# Power.net
KiCad netlist of a schematic drawn in Altium Designer
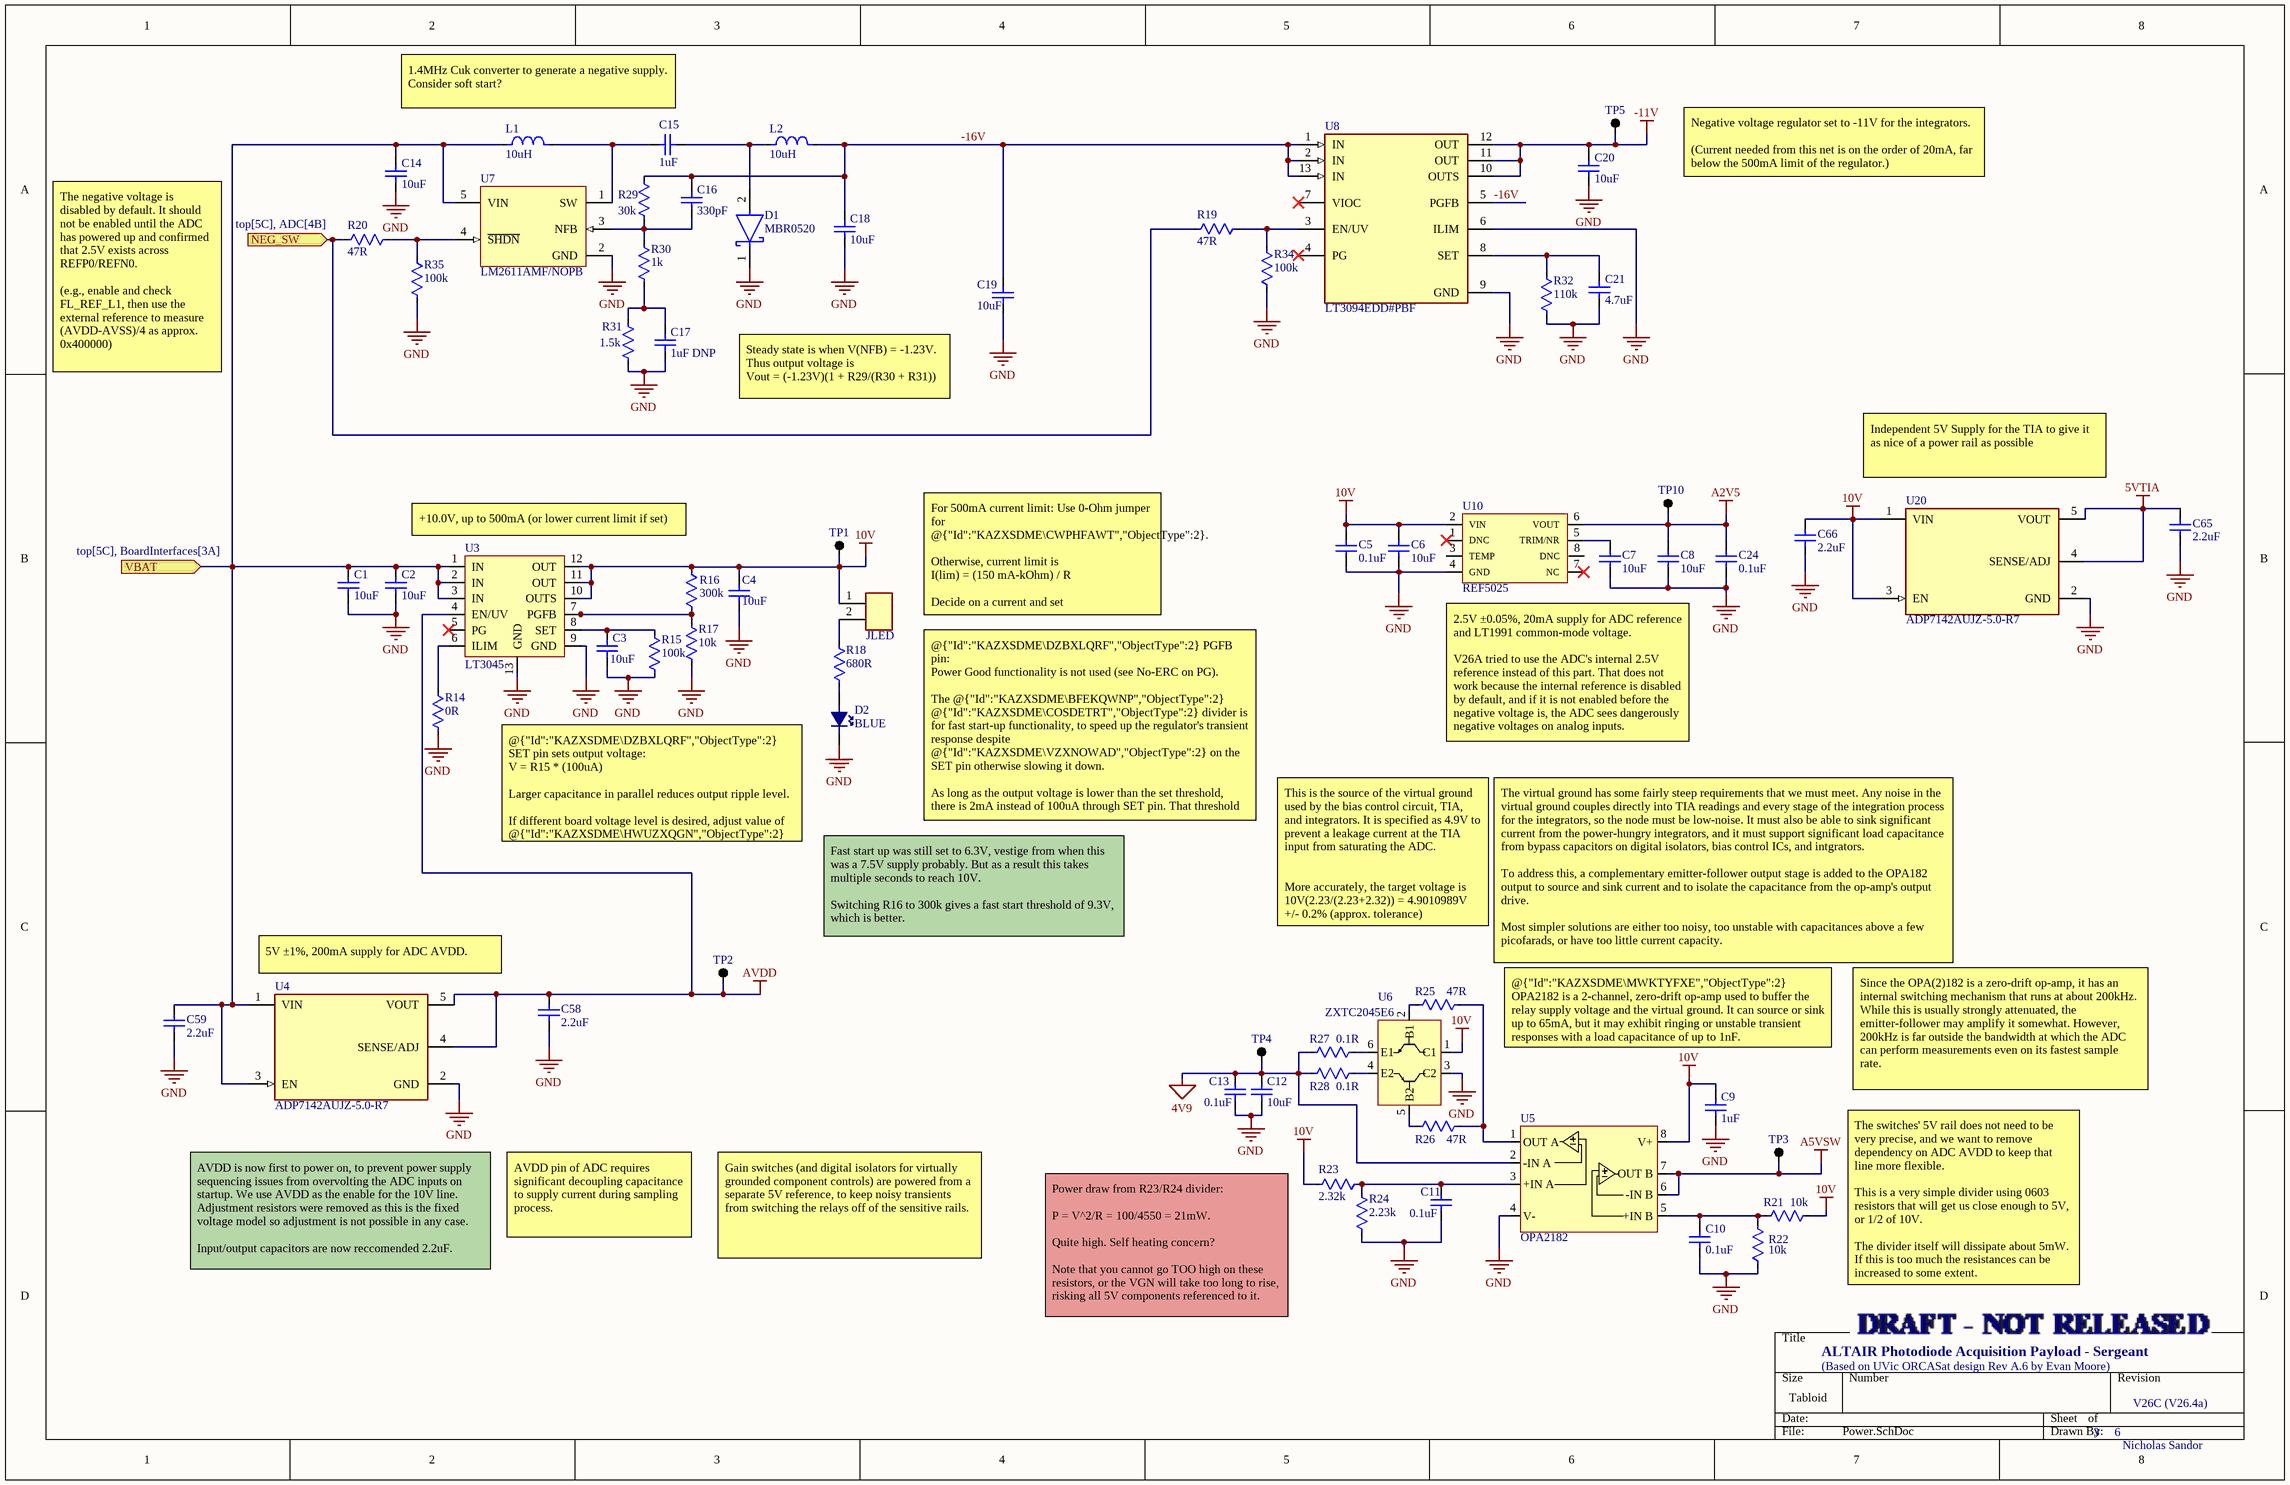
[diagram p0: Power.SchDoc]

(export (version "E")
  (design (tool "Eeschema 10.0.6"))
  (components
    (comp (ref "C1")
      (value "10uF")
      (footprint "CAP 1206 IPC LOW DENSITY")
      (description "Murata GRT319R6YA106KE01D - Cap Ceramic 10uF 35V X5R 10% Pad SMD 1206 85C Automotive T/R")
      (fields (field (name "MF") "Murata") (field (name "MP") "GRT319R6YA106KE01D"))
      (libsource (lib "ALTAIR_PD_Capacitors") (part "CAP"))
    )
    (comp (ref "C2")
      (value "10uF")
      (footprint "CAP 1206 IPC LOW DENSITY")
      (description "Murata GRT319R6YA106KE01D - Cap Ceramic 10uF 35V X5R 10% Pad SMD 1206 85C Automotive T/R")
      (fields (field (name "MF") "Murata") (field (name "MP") "GRT319R6YA106KE01D"))
      (libsource (lib "ALTAIR_PD_Capacitors") (part "CAP"))
    )
    (comp (ref "C3")
      (value "10uF")
      (footprint "CAP 1206 IPC LOW DENSITY")
      (description "Murata GRT319R6YA106KE01D - Cap Ceramic 10uF 35V X5R 10% Pad SMD 1206 85C Automotive T/R")
      (fields (field (name "MF") "Murata") (field (name "MP") "GRT319R6YA106KE01D"))
      (libsource (lib "ALTAIR_PD_Capacitors") (part "CAP"))
    )
    (comp (ref "C4")
      (value "10uF")
      (footprint "CAP 1206 IPC LOW DENSITY")
      (description "Murata GRT319R6YA106KE01D - Cap Ceramic 10uF 35V X5R 10% Pad SMD 1206 85C Automotive T/R")
      (fields (field (name "MF") "Murata") (field (name "MP") "GRT319R6YA106KE01D"))
      (libsource (lib "ALTAIR_PD_Capacitors") (part "CAP"))
    )
    (comp (ref "C5")
      (value "0.1uF")
      (footprint "CAP 0603 IPC MID DENSITY")
      (description "Kemet C0603C104K5RACAUTO - Cap Ceramic 0.1uF 50V X7R 10% 0603 125C Paper T/R")
      (fields (field (name "MF") "Kemet") (field (name "MP") "C0603C104K5RACAUTO"))
      (libsource (lib "ALTAIR_PD_Capacitors") (part "CAP"))
    )
    (comp (ref "C6")
      (value "10uF")
      (footprint "CAP 0805 IPC MID DENSITY")
      (description "Murata GRM21BR61E106KA73L - Cap Ceramic 10uF 10% 25V X5R 0805")
      (fields (field (name "MF") "Murata") (field (name "MP") "GRM21BR61E106KA73L"))
      (libsource (lib "ALTAIR_PD_Capacitors") (part "CAP"))
    )
    (comp (ref "C7")
      (value "10uF")
      (footprint "CAP 0805 IPC MID DENSITY")
      (description "Murata GRM21BR61E106KA73L - Cap Ceramic 10uF 10% 25V X5R 0805")
      (fields (field (name "MF") "Murata") (field (name "MP") "GRM21BR61E106KA73L"))
      (libsource (lib "ALTAIR_PD_Capacitors") (part "CAP"))
    )
    (comp (ref "C8")
      (value "10uF")
      (footprint "CAP 0805 IPC MID DENSITY")
      (description "Murata GRM21BR61E106KA73L - Cap Ceramic 10uF 10% 25V X5R 0805")
      (fields (field (name "MF") "Murata") (field (name "MP") "GRM21BR61E106KA73L"))
      (libsource (lib "ALTAIR_PD_Capacitors") (part "CAP"))
    )
    (comp (ref "C9")
      (value "1uF")
      (footprint "CAP 0603 IPC MID DENSITY")
      (description "Murata GRT188R61H105KE13D - Cap MLCC AEC-Q200 X5R 1uF 50V 0603")
      (fields (field (name "MF") "Murata") (field (name "MP") "GRT188R61H105KE13D"))
      (libsource (lib "ALTAIR_PD_Capacitors") (part "CAP"))
    )
    (comp (ref "C10")
      (value "0.1uF")
      (footprint "CAP 0603 IPC MID DENSITY")
      (description "Kemet C0603C104K5RACAUTO - Cap Ceramic 0.1uF 50V X7R 10% 0603 125C Paper T/R")
      (fields (field (name "MF") "Kemet") (field (name "MP") "C0603C104K5RACAUTO"))
      (libsource (lib "ALTAIR_PD_Capacitors") (part "CAP"))
    )
    (comp (ref "C11")
      (value "0.1uF")
      (footprint "CAP 0603 IPC MID DENSITY")
      (description "Kemet C0603C104K5RACAUTO - Cap Ceramic 0.1uF 50V X7R 10% 0603 125C Paper T/R")
      (fields (field (name "MF") "Kemet") (field (name "MP") "C0603C104K5RACAUTO"))
      (libsource (lib "ALTAIR_PD_Capacitors") (part "CAP"))
    )
    (comp (ref "C12")
      (value "10uF")
      (footprint "CAP 1206 IPC LOW DENSITY")
      (description "Murata GRT319R6YA106KE01D - Cap Ceramic 10uF 35V X5R 10% Pad SMD 1206 85C Automotive T/R")
      (fields (field (name "MF") "Murata") (field (name "MP") "GRT319R6YA106KE01D"))
      (libsource (lib "ALTAIR_PD_Capacitors") (part "CAP"))
    )
    (comp (ref "C13")
      (value "0.1uF")
      (footprint "CAP 0603 IPC MID DENSITY")
      (description "Kemet C0603C104K5RACAUTO - Cap Ceramic 0.1uF 50V X7R 10% 0603 125C Paper T/R")
      (fields (field (name "MF") "Kemet") (field (name "MP") "C0603C104K5RACAUTO"))
      (libsource (lib "ALTAIR_PD_Capacitors") (part "CAP"))
    )
    (comp (ref "C14")
      (value "10uF")
      (footprint "CAP 0805 IPC MID DENSITY")
      (description "Murata GRM21BR61E106KA73L - Cap Ceramic 10uF 10% 25V X5R 0805")
      (fields (field (name "MF") "Murata") (field (name "MP") "GRM21BR61E106KA73L"))
      (libsource (lib "ALTAIR_PD_Capacitors") (part "CAP"))
    )
    (comp (ref "C15")
      (value "1uF")
      (footprint "CAP 0603 IPC MID DENSITY")
      (description "Murata GRT188R61H105KE13D - Cap MLCC AEC-Q200 X5R 1uF 50V 0603")
      (fields (field (name "MF") "Murata") (field (name "MP") "GRT188R61H105KE13D"))
      (libsource (lib "ALTAIR_PD_Capacitors") (part "CAP"))
    )
    (comp (ref "C16")
      (value "330pF")
      (footprint "CAP 1206 NON-IPC KEMET NP0")
      (description "Kemet C1206C331J5GACTU - Cap Ceramic 330pF 50V 5% NP0 1206")
      (fields (field (name "MF") "Kemet") (field (name "MP") "C1206C331J5GACTU"))
      (libsource (lib "ALTAIR_PD_Capacitors") (part "CAP"))
    )
    (comp (ref "C17")
      (value "1uF DNP")
      (footprint "CAP 0603 IPC MID DENSITY")
      (description "Murata GRT188R61H105KE13D - Cap MLCC AEC-Q200 X5R 1uF 50V 0603")
      (fields (field (name "MF") "Murata") (field (name "MP") "GRT188R61H105KE13D"))
      (libsource (lib "ALTAIR_PD_Capacitors") (part "CAP"))
    )
    (comp (ref "C18")
      (value "10uF")
      (footprint "CAP 0805 IPC MID DENSITY")
      (description "Murata GRM21BR61E106KA73L - Cap Ceramic 10uF 10% 25V X5R 0805")
      (fields (field (name "MF") "Murata") (field (name "MP") "GRM21BR61E106KA73L"))
      (libsource (lib "ALTAIR_PD_Capacitors") (part "CAP"))
    )
    (comp (ref "C19")
      (value "10uF")
      (footprint "CAP 0805 IPC MID DENSITY")
      (description "Murata GRM21BR61E106KA73L - Cap Ceramic 10uF 10% 25V X5R 0805")
      (fields (field (name "MF") "Murata") (field (name "MP") "GRM21BR61E106KA73L"))
      (libsource (lib "ALTAIR_PD_Capacitors") (part "CAP"))
    )
    (comp (ref "C20")
      (value "10uF")
      (footprint "CAP 0805 IPC MID DENSITY")
      (description "Murata GRM21BR61E106KA73L - Cap Ceramic 10uF 10% 25V X5R 0805")
      (fields (field (name "MF") "Murata") (field (name "MP") "GRM21BR61E106KA73L"))
      (libsource (lib "ALTAIR_PD_Capacitors") (part "CAP"))
    )
    (comp (ref "C21")
      (value "4.7uF")
      (footprint "CAP 0805 NON-IPC KEMET X5R")
      (description "Kemet C0805C475K8PACTU - Cap Ceramic 4.7uF 10V X5R 0805")
      (fields (field (name "MF") "Kemet") (field (name "MP") "C0805C475K8PACTU"))
      (libsource (lib "ALTAIR_PD_Capacitors") (part "CAP"))
    )
    (comp (ref "C24")
      (value "0.1uF")
      (footprint "CAP 0603 IPC MID DENSITY")
      (description "Kemet C0603C104K5RACAUTO - Cap Ceramic 0.1uF 50V X7R 10% 0603 125C Paper T/R")
      (fields (field (name "MF") "Kemet") (field (name "MP") "C0603C104K5RACAUTO"))
      (libsource (lib "ALTAIR_PD_Capacitors") (part "CAP"))
    )
    (comp (ref "C58")
      (value "2.2uF")
      (footprint "CAP 1206 UNKNOWN")
      (description "Cap, Nonpolar, Any, Must choose footprint manually")
      (libsource (lib "ALTAIR_PD_Capacitors") (part "CAP"))
    )
    (comp (ref "C59")
      (value "2.2uF")
      (footprint "CAP 1206 UNKNOWN")
      (description "Cap, Nonpolar, Any, Must choose footprint manually")
      (libsource (lib "ALTAIR_PD_Capacitors") (part "CAP"))
    )
    (comp (ref "C65")
      (value "2.2uF")
      (footprint "CAP 1206 UNKNOWN")
      (description "Cap, Nonpolar, Any, Must choose footprint manually")
      (libsource (lib "ALTAIR_PD_Capacitors") (part "CAP"))
    )
    (comp (ref "C66")
      (value "2.2uF")
      (footprint "CAP 1206 UNKNOWN")
      (description "Cap, Nonpolar, Any, Must choose footprint manually")
      (libsource (lib "ALTAIR_PD_Capacitors") (part "CAP"))
    )
    (comp (ref "D1")
      (value "MBR0520")
      (footprint "SOD-123 ONSEMI SMALL PADS")
      (description "DIODE SCHOTTKY 20V 500MA SOD123")
      (fields (field (name "MF") "onsemi") (field (name "MP") "MBR0520LT1G"))
      (libsource (lib "ALTAIR_PD_Diodes") (part "Schottky"))
    )
    (comp (ref "D2")
      (value "BLUE")
      (footprint "LED 0603 MID DENSITY")
      (description "LED BLUE CLEAR 0603 SMD")
      (fields (field (name "MF") "Wurth Electronics") (field (name "MP") "150060BS75000"))
      (libsource (lib "ALTAIR_PD_Diodes") (part "LED-blue"))
    )
    (comp (ref "JLED")
      (value "JLED")
      (footprint "ALTAIR_PD_Headers:JUMPER 2POS 1MM PITCH THT")
      (description "2x1 Header THT 1mm Pitch")
      (fields
        (field (name "MF") "GCT (GLOBAL CONNECTOR TECHNOLOGY)")
        (field (name "MP") "BC020-02-A-0200-0300-L-G")
      )
      (libsource (lib "ALTAIR_PD_Headers") (part "BC020-02-A-0200-0300-L-G"))
    )
    (comp (ref "L1")
      (value "10uH")
      (footprint "IND VLS3012CX-1 NONSTANDARD TDK")
      (description "TDK VLS3012CX-100M-1 - Inductor 10uH 20% 1.25A 0.324Ohm NonstandardPkg")
      (fields (field (name "TOLERANCE") "20%") (field (name "MF") "TDK Corporation"))
      (libsource (lib "ALTAIR_PD_Inductors") (part "IND"))
    )
    (comp (ref "L2")
      (value "10uH")
      (footprint "IND VLS3012CX-1 NONSTANDARD TDK")
      (description "TDK VLS3012CX-100M-1 - Inductor 10uH 20% 1.25A 0.324Ohm NonstandardPkg")
      (fields (field (name "TOLERANCE") "20%") (field (name "MF") "TDK Corporation"))
      (libsource (lib "ALTAIR_PD_Inductors") (part "IND"))
    )
    (comp (ref "R14")
      (value "0R")
      (footprint "RES 0603 IPC MID DENSITY")
      (description "Vishay CRCW06030000Z0EA - Res 0 Ohms 1/8W SMD 0603")
      (fields (field (name "MF") "Vishay Dale") (field (name "MP") "CRCW06030000Z0EA"))
      (libsource (lib "ALTAIR_PD_Resistors") (part "RES"))
    )
    (comp (ref "R15")
      (value "100k")
      (footprint "RES 0603 IPC MID DENSITY")
      (description "Panasonic ERA-3ARB104V - Res SMD 0603 0.1% 0.10W T.C. 10ppm 100K")
      (fields (field (name "MF") "Panasonic Electronic Components") (field (name "MP") "ERA-3ARB104V"))
      (libsource (lib "ALTAIR_PD_Resistors") (part "RES"))
    )
    (comp (ref "R16")
      (value "300k")
      (footprint "RES 0603 IPC MID DENSITY")
      (description "Vishay MCT06030C2003FP500 - Res SMD 200kOhm 1% 1/10W 0603")
      (fields (field (name "MF") "Vishay Dale") (field (name "MP") "MCT06030C2003FP500"))
      (libsource (lib "ALTAIR_PD_Resistors") (part "RES"))
    )
    (comp (ref "R17")
      (value "10k")
      (footprint "RES 0603 IPC MID DENSITY")
      (description "Vishay CRCW060310K0FKEA SMD 0603 10k, CRCW e3 Series, 75V, thick film, 100mW")
      (fields (field (name "MF") "Vishay Dale") (field (name "MP") "CRCW060310K0FKEA"))
      (libsource (lib "ALTAIR_PD_Resistors") (part "RES"))
    )
    (comp (ref "R18")
      (value "680R")
      (footprint "RES 0603 IPC MID DENSITY")
      (description "Panasonic ERJ-3EKF6800V - Res SMD 680 Ohm 1% 1/10W 0603")
      (fields (field (name "MF") "Panasonic Electronic Components") (field (name "MP") "ERJ-3EKF6800V"))
      (libsource (lib "ALTAIR_PD_Resistors") (part "RES"))
    )
    (comp (ref "R19")
      (value "47R")
      (footprint "RES 0603 IPC MID DENSITY")
      (description "Vishay CRCW060347R0JNEA - Res 47Ohm 5% 1/8W SMD 0603")
      (fields (field (name "MF") "Vishay Dale") (field (name "MP") "CRCW060347R0JNEA"))
      (libsource (lib "ALTAIR_PD_Resistors") (part "RES"))
    )
    (comp (ref "R20")
      (value "47R")
      (footprint "RES 0603 IPC MID DENSITY")
      (description "Vishay CRCW060347R0JNEA - Res 47Ohm 5% 1/8W SMD 0603")
      (fields (field (name "MF") "Vishay Dale") (field (name "MP") "CRCW060347R0JNEA"))
      (libsource (lib "ALTAIR_PD_Resistors") (part "RES"))
    )
    (comp (ref "R21")
      (value "10k")
      (footprint "RES 0603 IPC MID DENSITY")
      (description "Vishay CRCW060310K0FKEA SMD 0603 10k, CRCW e3 Series, 75V, thick film, 100mW")
      (fields (field (name "MF") "Vishay Dale") (field (name "MP") "CRCW060310K0FKEA"))
      (libsource (lib "ALTAIR_PD_Resistors") (part "RES"))
    )
    (comp (ref "R22")
      (value "10k")
      (footprint "RES 0603 IPC MID DENSITY")
      (description "Vishay CRCW060310K0FKEA SMD 0603 10k, CRCW e3 Series, 75V, thick film, 100mW")
      (fields (field (name "MF") "Vishay Dale") (field (name "MP") "CRCW060310K0FKEA"))
      (libsource (lib "ALTAIR_PD_Resistors") (part "RES"))
    )
    (comp (ref "R23")
      (value "2.32k")
      (footprint "RES 0603 IPC MID DENSITY")
      (description "Vishay TNPW06032K32BEEA - Res 2.32k 0.1% 0.21W SMD 0603")
      (fields (field (name "MF") "Vishay Dale") (field (name "MP") "TNPW06032K32BEEA"))
      (libsource (lib "ALTAIR_PD_Resistors") (part "RES"))
    )
    (comp (ref "R24")
      (value "2.23k")
      (footprint "RES 0603 IPC MID DENSITY")
      (description "KOA Speer RN73R1JTTD2231B25 - Res 2.23k 0.1% 1/10W SMD 0603")
      (fields (field (name "MF") "KOA Speer Electronics, Inc.") (field (name "MP") "RN73R1JTTD2231B25"))
      (libsource (lib "ALTAIR_PD_Resistors") (part "RES"))
    )
    (comp (ref "R25")
      (value "47R")
      (footprint "RES 0402 NON-IPC SEI")
      (description "Stackpole RMCF0402JT47R0 - Res 47Ohm 5% 0.063W 0402 Thick Film AEC-Q200 compliant")
      (fields (field (name "MF") "Stackpole Electronics Inc.") (field (name "MP") "RMCF0402JT47R0"))
      (libsource (lib "ALTAIR_PD_Resistors") (part "RES"))
    )
    (comp (ref "R26")
      (value "47R")
      (footprint "RES 0402 NON-IPC SEI")
      (description "Stackpole RMCF0402JT47R0 - Res 47Ohm 5% 0.063W 0402 Thick Film AEC-Q200 compliant")
      (fields (field (name "MF") "Stackpole Electronics Inc.") (field (name "MP") "RMCF0402JT47R0"))
      (libsource (lib "ALTAIR_PD_Resistors") (part "RES"))
    )
    (comp (ref "R27")
      (value "0.1R")
      (footprint "RES 0402 NON-IPC YAGEO")
      (description "Yageo RL0402JR-070R1L - Res 0.1Ohm 5% 1/16W SMD 0402")
      (fields (field (name "MF") "YAGEO") (field (name "MP") "RL0402JR-070R1L"))
      (libsource (lib "ALTAIR_PD_Resistors") (part "RES"))
    )
    (comp (ref "R28")
      (value "0.1R")
      (footprint "RES 0402 NON-IPC YAGEO")
      (description "Yageo RL0402JR-070R1L - Res 0.1Ohm 5% 1/16W SMD 0402")
      (fields (field (name "MF") "YAGEO") (field (name "MP") "RL0402JR-070R1L"))
      (libsource (lib "ALTAIR_PD_Resistors") (part "RES"))
    )
    (comp (ref "R29")
      (value "30k")
      (footprint "RES 0805 IPC HIGH DENSITY")
      (description "Panasonic ERA-6AEB303V - Res 30kOhm 0.1% 1/8W 0805")
      (fields (field (name "MF") "Panasonic Electronic Components") (field (name "MP") "ERA-6AEB303V"))
      (libsource (lib "ALTAIR_PD_Resistors") (part "RES"))
    )
    (comp (ref "R30")
      (value "1k")
      (footprint "RES 0402 IPC LOW DENSITY YAGEO")
      (description "Yageo RC0402FR-071KL - Res 1kOhm 1% 1/16W 0402")
      (fields (field (name "MF") "YAGEO") (field (name "MP") "RC0402FR-071KL"))
      (libsource (lib "ALTAIR_PD_Resistors") (part "RES"))
    )
    (comp (ref "R31")
      (value "1.5k")
      (footprint "RES 1206 NON-IPC VISHAY")
      (description "Vishay TNPU12061K50BZEN00 - Res 1.5kOhm 0.1% 1/4W 1206")
      (fields (field (name "MF") "Vishay Dale") (field (name "MP") "TNPU12061K50BZEN00"))
      (libsource (lib "ALTAIR_PD_Resistors") (part "RES"))
    )
    (comp (ref "R32")
      (value "110k")
      (footprint "RES 0603 IPC MID DENSITY")
      (description "Panasonic ERA-3AEB114V - Res 110k 0.1% 1/10W SMD 0603")
      (fields (field (name "MF") "Panasonic Electronic Components") (field (name "MP") "ERA-3AEB114V"))
      (libsource (lib "ALTAIR_PD_Resistors") (part "RES"))
    )
    (comp (ref "R34")
      (value "100k")
      (footprint "RES 0603 IPC MID DENSITY")
      (description "Panasonic ERJ-3GEYJ104V - Res 100k 5% 1/10W SMD 0603")
      (fields (field (name "MF") "Panasonic Electronic Components") (field (name "MP") "ERJ-3GEYJ104V"))
      (libsource (lib "ALTAIR_PD_Resistors") (part "RES"))
    )
    (comp (ref "R35")
      (value "100k")
      (footprint "RES 0603 IPC MID DENSITY")
      (description "Panasonic ERJ-3GEYJ104V - Res 100k 5% 1/10W SMD 0603")
      (fields (field (name "MF") "Panasonic Electronic Components") (field (name "MP") "ERJ-3GEYJ104V"))
      (libsource (lib "ALTAIR_PD_Resistors") (part "RES"))
    )
    (comp (ref "TP1")
      (value "Testpoint")
      (footprint "TESTPOINT THT")
      (libsource (lib "ALTAIR_PD_Testpoint") (part "Testpoint"))
    )
    (comp (ref "TP2")
      (value "Testpoint")
      (footprint "TESTPOINT THT")
      (libsource (lib "ALTAIR_PD_Testpoint") (part "Testpoint"))
    )
    (comp (ref "TP3")
      (value "Testpoint")
      (footprint "TESTPOINT THT")
      (libsource (lib "ALTAIR_PD_Testpoint") (part "Testpoint"))
    )
    (comp (ref "TP4")
      (value "Testpoint")
      (footprint "TESTPOINT THT")
      (libsource (lib "ALTAIR_PD_Testpoint") (part "Testpoint"))
    )
    (comp (ref "TP5")
      (value "Testpoint")
      (footprint "TESTPOINT THT")
      (libsource (lib "ALTAIR_PD_Testpoint") (part "Testpoint"))
    )
    (comp (ref "TP10")
      (value "Testpoint")
      (footprint "TESTPOINT THT")
      (libsource (lib "ALTAIR_PD_Testpoint") (part "Testpoint"))
    )
    (comp (ref "U3")
      (value "LT3045")
      (footprint "12-TSOP 0.65MM PITCH 3MM WIDTH EP IPC MID DENSITY")
      (description "20V 500mA Ultralow Noise Ultrahigh PSRR Adjustable Linear Regulator 260V Dropout MSOP-12")
      (fields (field (name "MF") "Analog Devices / Linear Technology") (field (name "MP") "LT3045EMSE#PBF"))
      (libsource (lib "ALTAIR_PD_Regulators") (part "LT3045"))
    )
    (comp (ref "U4")
      (value "ADP7142AUJZ-5.0-R7")
      (footprint "SOT23-5 HIGH DENSITY AD")
      (description "1.2-40V 200mA Low Noise CMOS LDO Adjustable Linear Regulator TSOT23")
      (fields
        (field (name "OCTOPART") "https://octopart.com/adp7142aujz-r7-analog+devices-38928114")
        (field (name "MF") "Analog Devices")
      )
      (libsource (lib "ALTAIR_PD_Regulators") (part "ADP7142AUJZ-R7"))
    )
    (comp (ref "U5")
      (value "OPA2182")
      (footprint "8-TSSOP 0.65MM PITCH 4.4MM WIDTH IPC MID DENSITY")
      (fields (field (name "MF") "Texas Instruments") (field (name "MP") "OPA2182IDGKR"))
      (libsource (lib "ALTAIR_PD_Amplifiers") (part "OPA2182IDBV"))
    )
    (comp (ref "U6")
      (value "ZXTC2045E6")
      (footprint "SOT23-6 NON-IPC DIODES")
      (description "BJT Array, 1NPN 1PNP, VCE(sat) 375mV, hFE 300, Breakdown 30V, 6-SOT-23")
      (fields (field (name "MF") "Diodes Incorporated") (field (name "MP") "ZXTC2045E6TA"))
      (libsource (lib "ALTAIR_PD_BJTs") (part "ZXTC2045E6"))
    )
    (comp (ref "U7")
      (value "LM2611AMF/NOPB")
      (footprint "SOT23-5 MID DENSITY")
      (description "1.4MHz Cuk Converter, 5-pin SOT-23, Pb-Free")
      (fields (field (name "MF") "Texas Instruments"))
      (libsource (lib "ALTAIR_PD_Converters") (part "LM2611AMF"))
    )
    (comp (ref "U8")
      (value "LT3094EDD#PBF")
      (footprint "12DFN 3x3MM EP IPC MID DENSITY")
      (description "-20V 500mA Ultralow Noise Ultrahigh PSRR Adjustable Negative Linear Regulator 12DFN")
      (fields (field (name "MF") "Analog Devices"))
      (libsource (lib "ALTAIR_PD_Regulators") (part "LT3094EDD#PBF"))
    )
    (comp (ref "U10")
      (value "REF5025")
      (footprint "8-TSOP 0.65MM PITCH 3MM WIDTH IPC MID DENSITY")
      (description "2.5V±0.05% Voltage Reference 8VSSOP")
      (fields (field (name "MF") "Texas Instruments") (field (name "MP") "REF5025IDGKR"))
      (libsource (lib "ALTAIR_PD_MiscPower") (part "REF5050IDGKR"))
    )
    (comp (ref "U20")
      (value "ADP7142AUJZ-5.0-R7")
      (footprint "SOT23-5 HIGH DENSITY AD")
      (description "1.2-40V 200mA Low Noise CMOS LDO Adjustable Linear Regulator TSOT23")
      (fields
        (field (name "OCTOPART") "https://octopart.com/adp7142aujz-r7-analog+devices-38928114")
        (field (name "MF") "Analog Devices")
      )
      (libsource (lib "ALTAIR_PD_Regulators") (part "ADP7142AUJZ-R7"))
    )
  )
  (nets
    (net (code "1") (name "-11V") (class "Default")
      (node (ref "C20") (pin "1") (pinfunction "1_1") (pintype "passive"))
      (node (ref "TP5") (pin "1") (pinfunction "1_1") (pintype "passive"))
      (node (ref "U8") (pin "10") (pinfunction "OUTS_10") (pintype "power_in"))
      (node (ref "U8") (pin "11") (pinfunction "OUT_11") (pintype "power_in"))
      (node (ref "U8") (pin "12") (pinfunction "OUT_12") (pintype "power_in"))
    )
    (net (code "2") (name "/-16V") (class "Default")
      (node (ref "C16") (pin "1") (pinfunction "1_1") (pintype "passive"))
      (node (ref "C18") (pin "1") (pinfunction "1_1") (pintype "passive"))
      (node (ref "C19") (pin "1") (pinfunction "1_1") (pintype "passive"))
      (node (ref "L2") (pin "2") (pinfunction "2_2") (pintype "passive"))
      (node (ref "R29") (pin "2") (pinfunction "2_2") (pintype "passive"))
      (node (ref "U8") (pin "1") (pinfunction "IN_1") (pintype "input"))
      (node (ref "U8") (pin "13") (pinfunction "IN_13") (pintype "input"))
      (node (ref "U8") (pin "2") (pinfunction "IN_2") (pintype "input"))
      (node (ref "U8") (pin "5") (pinfunction "PGFB_5") (pintype "passive"))
    )
    (net (code "3") (name "/NEG_SW") (class "Default")
      (node (ref "R19") (pin "2") (pinfunction "2_2") (pintype "passive"))
      (node (ref "R20") (pin "2") (pinfunction "2_2") (pintype "passive"))
    )
    (net (code "4") (name "/VBAT") (class "Default")
      (node (ref "C1") (pin "2") (pinfunction "2_2") (pintype "passive"))
      (node (ref "C14") (pin "2") (pinfunction "2_2") (pintype "passive"))
      (node (ref "C2") (pin "2") (pinfunction "2_2") (pintype "passive"))
      (node (ref "C59") (pin "1") (pinfunction "1_1") (pintype "passive"))
      (node (ref "L1") (pin "1") (pinfunction "1_1") (pintype "passive"))
      (node (ref "U3") (pin "1") (pinfunction "IN_1") (pintype "passive"))
      (node (ref "U3") (pin "2") (pinfunction "IN_2") (pintype "passive"))
      (node (ref "U3") (pin "3") (pinfunction "IN_3") (pintype "passive"))
      (node (ref "U4") (pin "1") (pinfunction "VIN_1") (pintype "power_in"))
      (node (ref "U4") (pin "3") (pinfunction "EN_3") (pintype "input"))
      (node (ref "U7") (pin "5") (pinfunction "VIN_5") (pintype "power_in"))
    )
    (net (code "5") (name "4V9") (class "Default")
      (node (ref "C12") (pin "2") (pinfunction "2_2") (pintype "passive"))
      (node (ref "C13") (pin "2") (pinfunction "2_2") (pintype "passive"))
      (node (ref "R27") (pin "1") (pinfunction "1_1") (pintype "passive"))
      (node (ref "R28") (pin "1") (pinfunction "1_1") (pintype "passive"))
      (node (ref "TP4") (pin "1") (pinfunction "1_1") (pintype "passive"))
      (node (ref "U5") (pin "2") (pinfunction "-IN_A_2") (pintype "passive"))
    )
    (net (code "6") (name "5VTIA") (class "Default")
      (node (ref "C65") (pin "1") (pinfunction "1_1") (pintype "passive"))
      (node (ref "U20") (pin "4") (pinfunction "SENSE/ADJ_4") (pintype "passive"))
      (node (ref "U20") (pin "5") (pinfunction "VOUT_5") (pintype "passive"))
    )
    (net (code "7") (name "10V") (class "Default")
      (node (ref "C4") (pin "2") (pinfunction "2_2") (pintype "passive"))
      (node (ref "C5") (pin "1") (pinfunction "1_1") (pintype "passive"))
      (node (ref "C6") (pin "2") (pinfunction "2_2") (pintype "passive"))
      (node (ref "C66") (pin "1") (pinfunction "1_1") (pintype "passive"))
      (node (ref "C9") (pin "2") (pinfunction "2_2") (pintype "passive"))
      (node (ref "JLED") (pin "1") (pinfunction "1_1") (pintype "passive"))
      (node (ref "R16") (pin "2") (pinfunction "2_2") (pintype "passive"))
      (node (ref "R21") (pin "2") (pinfunction "2_2") (pintype "passive"))
      (node (ref "R23") (pin "2") (pinfunction "2_2") (pintype "passive"))
      (node (ref "TP1") (pin "1") (pinfunction "1_1") (pintype "passive"))
      (node (ref "U10") (pin "2") (pinfunction "VIN_2") (pintype "passive"))
      (node (ref "U20") (pin "1") (pinfunction "VIN_1") (pintype "power_in"))
      (node (ref "U20") (pin "3") (pinfunction "EN_3") (pintype "input"))
      (node (ref "U3") (pin "10") (pinfunction "OUTS_10") (pintype "passive"))
      (node (ref "U3") (pin "11") (pinfunction "OUT_11") (pintype "passive"))
      (node (ref "U3") (pin "12") (pinfunction "OUT_12") (pintype "passive"))
      (node (ref "U5") (pin "8") (pinfunction "V+_8") (pintype "passive"))
      (node (ref "U6") (pin "1") (pinfunction "C1_1") (pintype "passive"))
    )
    (net (code "8") (name "A2V5") (class "Default")
      (node (ref "C24") (pin "1") (pinfunction "1_1") (pintype "passive"))
      (node (ref "C8") (pin "2") (pinfunction "2_2") (pintype "passive"))
      (node (ref "TP10") (pin "1") (pinfunction "1_1") (pintype "passive"))
      (node (ref "U10") (pin "6") (pinfunction "VOUT_6") (pintype "passive"))
    )
    (net (code "9") (name "A5VSW") (class "Default")
      (node (ref "TP3") (pin "1") (pinfunction "1_1") (pintype "passive"))
      (node (ref "U5") (pin "6") (pinfunction "-IN_B_6") (pintype "passive"))
      (node (ref "U5") (pin "7") (pinfunction "OUT_B_7") (pintype "passive"))
    )
    (net (code "10") (name "AVDD") (class "Default")
      (node (ref "C58") (pin "1") (pinfunction "1_1") (pintype "passive"))
      (node (ref "TP2") (pin "1") (pinfunction "1_1") (pintype "passive"))
      (node (ref "U3") (pin "4") (pinfunction "EN/UV_4") (pintype "passive"))
      (node (ref "U4") (pin "4") (pinfunction "SENSE/ADJ_4") (pintype "passive"))
      (node (ref "U4") (pin "5") (pinfunction "VOUT_5") (pintype "passive"))
    )
    (net (code "11") (name "GND") (class "Default")
      (node (ref "C1") (pin "1") (pinfunction "1_1") (pintype "passive"))
      (node (ref "C10") (pin "1") (pinfunction "1_1") (pintype "passive"))
      (node (ref "C11") (pin "1") (pinfunction "1_1") (pintype "passive"))
      (node (ref "C12") (pin "1") (pinfunction "1_1") (pintype "passive"))
      (node (ref "C13") (pin "1") (pinfunction "1_1") (pintype "passive"))
      (node (ref "C14") (pin "1") (pinfunction "1_1") (pintype "passive"))
      (node (ref "C17") (pin "2") (pinfunction "2_2") (pintype "passive"))
      (node (ref "C18") (pin "2") (pinfunction "2_2") (pintype "passive"))
      (node (ref "C19") (pin "2") (pinfunction "2_2") (pintype "passive"))
      (node (ref "C2") (pin "1") (pinfunction "1_1") (pintype "passive"))
      (node (ref "C20") (pin "2") (pinfunction "2_2") (pintype "passive"))
      (node (ref "C21") (pin "2") (pinfunction "2_2") (pintype "passive"))
      (node (ref "C24") (pin "2") (pinfunction "2_2") (pintype "passive"))
      (node (ref "C3") (pin "1") (pinfunction "1_1") (pintype "passive"))
      (node (ref "C4") (pin "1") (pinfunction "1_1") (pintype "passive"))
      (node (ref "C5") (pin "2") (pinfunction "2_2") (pintype "passive"))
      (node (ref "C58") (pin "2") (pinfunction "2_2") (pintype "passive"))
      (node (ref "C59") (pin "2") (pinfunction "2_2") (pintype "passive"))
      (node (ref "C6") (pin "1") (pinfunction "1_1") (pintype "passive"))
      (node (ref "C65") (pin "2") (pinfunction "2_2") (pintype "passive"))
      (node (ref "C66") (pin "2") (pinfunction "2_2") (pintype "passive"))
      (node (ref "C7") (pin "2") (pinfunction "2_2") (pintype "passive"))
      (node (ref "C8") (pin "1") (pinfunction "1_1") (pintype "passive"))
      (node (ref "C9") (pin "1") (pinfunction "1_1") (pintype "passive"))
      (node (ref "D1") (pin "1") (pinfunction "C_1") (pintype "passive"))
      (node (ref "D2") (pin "1") (pinfunction "1_1") (pintype "passive"))
      (node (ref "R14") (pin "1") (pinfunction "1_1") (pintype "passive"))
      (node (ref "R15") (pin "1") (pinfunction "1_1") (pintype "passive"))
      (node (ref "R17") (pin "1") (pinfunction "1_1") (pintype "passive"))
      (node (ref "R22") (pin "1") (pinfunction "1_1") (pintype "passive"))
      (node (ref "R24") (pin "1") (pinfunction "1_1") (pintype "passive"))
      (node (ref "R31") (pin "1") (pinfunction "1_1") (pintype "passive"))
      (node (ref "R32") (pin "2") (pinfunction "2_2") (pintype "passive"))
      (node (ref "R34") (pin "2") (pinfunction "2_2") (pintype "passive"))
      (node (ref "R35") (pin "2") (pinfunction "2_2") (pintype "passive"))
      (node (ref "U10") (pin "4") (pinfunction "GND_4") (pintype "passive"))
      (node (ref "U20") (pin "2") (pinfunction "GND_2") (pintype "power_in"))
      (node (ref "U3") (pin "13") (pinfunction "GND_13") (pintype "passive"))
      (node (ref "U3") (pin "9") (pinfunction "GND_9") (pintype "passive"))
      (node (ref "U4") (pin "2") (pinfunction "GND_2") (pintype "power_in"))
      (node (ref "U5") (pin "4") (pinfunction "V-_4") (pintype "passive"))
      (node (ref "U6") (pin "3") (pinfunction "C2_3") (pintype "passive"))
      (node (ref "U7") (pin "2") (pinfunction "GND_2") (pintype "power_in"))
      (node (ref "U8") (pin "6") (pinfunction "ILIM_6") (pintype "passive"))
      (node (ref "U8") (pin "9") (pinfunction "GND_9") (pintype "power_in"))
    )
    (net (code "12") (name "Net-(C17-Pad1)") (class "Default")
      (node (ref "C17") (pin "1") (pinfunction "1_1") (pintype "passive"))
      (node (ref "R30") (pin "1") (pinfunction "1_1") (pintype "passive"))
      (node (ref "R31") (pin "2") (pinfunction "2_2") (pintype "passive"))
    )
    (net (code "13") (name "Net-(D1-A)") (class "Default")
      (node (ref "C15") (pin "2") (pinfunction "2_2") (pintype "passive"))
      (node (ref "D1") (pin "2") (pinfunction "A_2") (pintype "passive"))
      (node (ref "L2") (pin "1") (pinfunction "1_1") (pintype "passive"))
    )
    (net (code "14") (name "Net-(D2-Pad2)") (class "Default")
      (node (ref "D2") (pin "2") (pinfunction "2_2") (pintype "passive"))
      (node (ref "R18") (pin "1") (pinfunction "1_1") (pintype "passive"))
    )
    (net (code "15") (name "Net-(JLED-Pad2)") (class "Default")
      (node (ref "JLED") (pin "2") (pinfunction "2_2") (pintype "passive"))
      (node (ref "R18") (pin "2") (pinfunction "2_2") (pintype "passive"))
    )
    (net (code "16") (name "Net-(U3-ILIM)") (class "Default")
      (node (ref "R14") (pin "2") (pinfunction "2_2") (pintype "passive"))
      (node (ref "U3") (pin "6") (pinfunction "ILIM_6") (pintype "passive"))
    )
    (net (code "17") (name "Net-(U3-PGFB)") (class "Default")
      (node (ref "R16") (pin "1") (pinfunction "1_1") (pintype "passive"))
      (node (ref "R17") (pin "2") (pinfunction "2_2") (pintype "passive"))
      (node (ref "U3") (pin "7") (pinfunction "PGFB_7") (pintype "passive"))
    )
    (net (code "18") (name "Net-(U3-SET)") (class "Default")
      (node (ref "C3") (pin "2") (pinfunction "2_2") (pintype "passive"))
      (node (ref "R15") (pin "2") (pinfunction "2_2") (pintype "passive"))
      (node (ref "U3") (pin "8") (pinfunction "SET_8") (pintype "passive"))
    )
    (net (code "19") (name "Net-(U5-+IN_A)") (class "Default")
      (node (ref "C11") (pin "2") (pinfunction "2_2") (pintype "passive"))
      (node (ref "R23") (pin "1") (pinfunction "1_1") (pintype "passive"))
      (node (ref "R24") (pin "2") (pinfunction "2_2") (pintype "passive"))
      (node (ref "U5") (pin "3") (pinfunction "+IN_A_3") (pintype "passive"))
    )
    (net (code "20") (name "Net-(U5-+IN_B)") (class "Default")
      (node (ref "C10") (pin "2") (pinfunction "2_2") (pintype "passive"))
      (node (ref "R21") (pin "1") (pinfunction "1_1") (pintype "passive"))
      (node (ref "R22") (pin "2") (pinfunction "2_2") (pintype "passive"))
      (node (ref "U5") (pin "5") (pinfunction "+IN_B_5") (pintype "passive"))
    )
    (net (code "21") (name "Net-(U5-OUT_A)") (class "Default")
      (node (ref "R25") (pin "2") (pinfunction "2_2") (pintype "passive"))
      (node (ref "R26") (pin "2") (pinfunction "2_2") (pintype "passive"))
      (node (ref "U5") (pin "1") (pinfunction "OUT_A_1") (pintype "passive"))
    )
    (net (code "22") (name "Net-(U6-B1)") (class "Default")
      (node (ref "R25") (pin "1") (pinfunction "1_1") (pintype "passive"))
      (node (ref "U6") (pin "2") (pinfunction "B1_2") (pintype "passive"))
    )
    (net (code "23") (name "Net-(U6-B2)") (class "Default")
      (node (ref "R26") (pin "1") (pinfunction "1_1") (pintype "passive"))
      (node (ref "U6") (pin "5") (pinfunction "B2_5") (pintype "passive"))
    )
    (net (code "24") (name "Net-(U6-E1)") (class "Default")
      (node (ref "R27") (pin "2") (pinfunction "2_2") (pintype "passive"))
      (node (ref "U6") (pin "6") (pinfunction "E1_6") (pintype "passive"))
    )
    (net (code "25") (name "Net-(U6-E2)") (class "Default")
      (node (ref "R28") (pin "2") (pinfunction "2_2") (pintype "passive"))
      (node (ref "U6") (pin "4") (pinfunction "E2_4") (pintype "passive"))
    )
    (net (code "26") (name "Net-(U7-NFB)") (class "Default")
      (node (ref "C16") (pin "2") (pinfunction "2_2") (pintype "passive"))
      (node (ref "R29") (pin "1") (pinfunction "1_1") (pintype "passive"))
      (node (ref "R30") (pin "2") (pinfunction "2_2") (pintype "passive"))
      (node (ref "U7") (pin "3") (pinfunction "NFB_3") (pintype "input"))
    )
    (net (code "27") (name "Net-(U7-SW)") (class "Default")
      (node (ref "C15") (pin "1") (pinfunction "1_1") (pintype "passive"))
      (node (ref "L1") (pin "2") (pinfunction "2_2") (pintype "passive"))
      (node (ref "U7") (pin "1") (pinfunction "SW_1") (pintype "power_in"))
    )
    (net (code "28") (name "Net-(U7-~{SHDN})") (class "Default")
      (node (ref "R20") (pin "1") (pinfunction "1_1") (pintype "passive"))
      (node (ref "R35") (pin "1") (pinfunction "1_1") (pintype "passive"))
      (node (ref "U7") (pin "4") (pinfunction "~{SHDN}_4") (pintype "input"))
    )
    (net (code "29") (name "Net-(U8-EN{slash}UV)") (class "Default")
      (node (ref "R19") (pin "1") (pinfunction "1_1") (pintype "passive"))
      (node (ref "R34") (pin "1") (pinfunction "1_1") (pintype "passive"))
      (node (ref "U8") (pin "3") (pinfunction "EN/UV_3") (pintype "passive"))
    )
    (net (code "30") (name "Net-(U8-SET)") (class "Default")
      (node (ref "C21") (pin "1") (pinfunction "1_1") (pintype "passive"))
      (node (ref "R32") (pin "1") (pinfunction "1_1") (pintype "passive"))
      (node (ref "U8") (pin "8") (pinfunction "SET_8") (pintype "passive"))
    )
    (net (code "31") (name "Net-(U10-TRIM{slash}NR)") (class "Default")
      (node (ref "C7") (pin "1") (pinfunction "1_1") (pintype "passive"))
      (node (ref "U10") (pin "5") (pinfunction "TRIM/NR_5") (pintype "passive"))
    )
    (net (code "32") (name "unconnected-(U3-PG-Pad5)") (class "Default")
      (node (ref "U3") (pin "5") (pinfunction "PG_5") (pintype "passive+no_connect"))
    )
    (net (code "33") (name "unconnected-(U8-PG-Pad4)") (class "Default")
      (node (ref "U8") (pin "4") (pinfunction "PG_4") (pintype "passive+no_connect"))
    )
    (net (code "34") (name "unconnected-(U8-VIOC-Pad7)") (class "Default")
      (node (ref "U8") (pin "7") (pinfunction "VIOC_7") (pintype "passive+no_connect"))
    )
    (net (code "35") (name "unconnected-(U10-DNC-Pad1)") (class "Default")
      (node (ref "U10") (pin "1") (pinfunction "DNC_1") (pintype "passive+no_connect"))
    )
    (net (code "36") (name "unconnected-(U10-DNC-Pad8)") (class "Default")
      (node (ref "U10") (pin "8") (pinfunction "DNC_8") (pintype "passive"))
    )
    (net (code "37") (name "unconnected-(U10-NC-Pad7)") (class "Default")
      (node (ref "U10") (pin "7") (pinfunction "NC_7") (pintype "passive+no_connect"))
    )
    (net (code "38") (name "unconnected-(U10-TEMP-Pad3)") (class "Default")
      (node (ref "U10") (pin "3") (pinfunction "TEMP_3") (pintype "passive"))
    )
  )
)
